# Sheet3_Fontes_Chaveadas_Fontes_Aux.net
KiCad netlist of a schematic drawn in Altium Designer
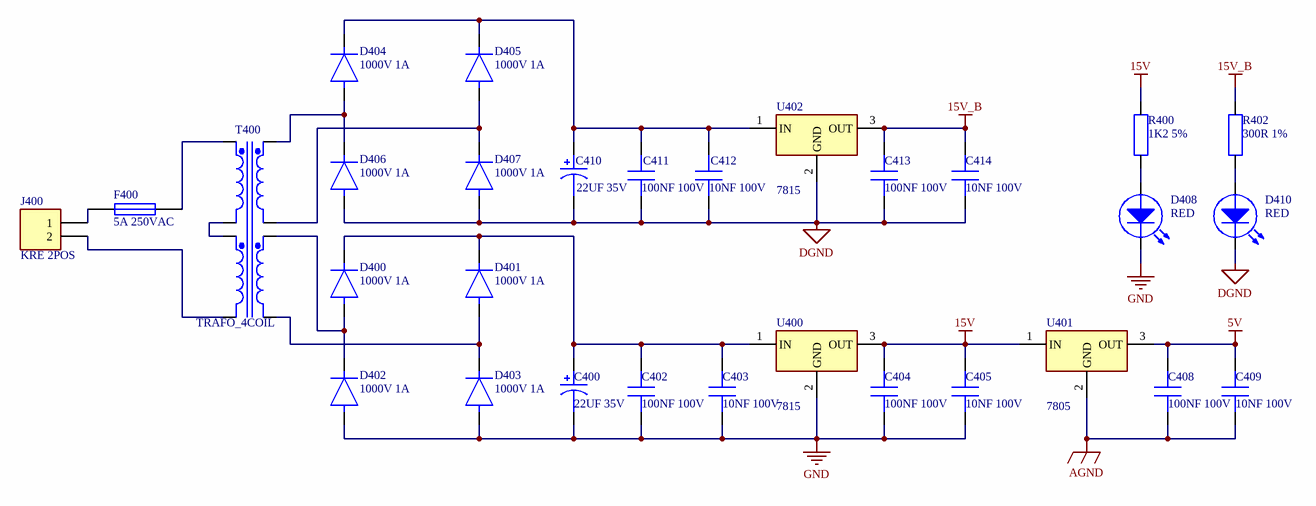
[diagram p0: Sheet3_Fontes_Chaveadas_Fontes_Aux.SchDoc]

(export (version "E")
  (design (tool "Eeschema 10.0.6"))
  (components
    (comp (ref "C400")
      (value "22UF 35V")
      (footprint "PcbLib_Fontes_Chaveadas:CAP_RAD_D6MM3_L2MM5")
      (description "CAP ALUM POLY 22UF 20% 35V T/H")
      (fields (field (name "PARTNUMBER") "870055673002") (field (name "DKPART") "732-6368-1-ND"))
      (libsource (lib "Schlib_Fontes_Chaveadas") (part "CAP_ALUM_22UF_35V_RAD"))
    )
    (comp (ref "C402")
      (value "100NF 100V")
      (footprint "PcbLib_Fontes_Chaveadas:CAP_RAD_4X2MM5")
      (description "CAP CER 0.1UF 100V X7S RADIAL")
      (fields (field (name "PARTNUMBER") "FG18X7S2A104KRT06") (field (name "DKPART") "445-173281-1-ND"))
      (libsource (lib "Schlib_Fontes_Chaveadas") (part "CAP_CER_100NF_100V_RAD"))
    )
    (comp (ref "C403")
      (value "10NF 100V")
      (footprint "PcbLib_Fontes_Chaveadas:CAP_RAD_4X2MM5")
      (description "CAP CER 10NF 100V C0G/NP0 RADIAL")
      (fields (field (name "PARTNUMBER") "FA18C0G2A103JRU06") (field (name "DKPART") "445-175393-1-ND"))
      (libsource (lib "Schlib_Fontes_Chaveadas") (part "CAP_CER_10NF_100V_RAD"))
    )
    (comp (ref "C404")
      (value "100NF 100V")
      (footprint "PcbLib_Fontes_Chaveadas:CAP_RAD_4X2MM5")
      (description "CAP CER 0.1UF 100V X7S RADIAL")
      (fields (field (name "PARTNUMBER") "FG18X7S2A104KRT06") (field (name "DKPART") "445-173281-1-ND"))
      (libsource (lib "Schlib_Fontes_Chaveadas") (part "CAP_CER_100NF_100V_RAD"))
    )
    (comp (ref "C405")
      (value "10NF 100V")
      (footprint "PcbLib_Fontes_Chaveadas:CAP_RAD_4X2MM5")
      (description "CAP CER 10NF 100V C0G/NP0 RADIAL")
      (fields (field (name "PARTNUMBER") "FA18C0G2A103JRU06") (field (name "DKPART") "445-175393-1-ND"))
      (libsource (lib "Schlib_Fontes_Chaveadas") (part "CAP_CER_10NF_100V_RAD"))
    )
    (comp (ref "C408")
      (value "100NF 100V")
      (footprint "PcbLib_Fontes_Chaveadas:CAP_RAD_4X2MM5")
      (description "CAP CER 0.1UF 100V X7S RADIAL")
      (fields (field (name "PARTNUMBER") "FG18X7S2A104KRT06") (field (name "DKPART") "445-173281-1-ND"))
      (libsource (lib "Schlib_Fontes_Chaveadas") (part "CAP_CER_100NF_100V_RAD"))
    )
    (comp (ref "C409")
      (value "10NF 100V")
      (footprint "PcbLib_Fontes_Chaveadas:CAP_RAD_4X2MM5")
      (description "CAP CER 10NF 100V C0G/NP0 RADIAL")
      (fields (field (name "PARTNUMBER") "FA18C0G2A103JRU06") (field (name "DKPART") "445-175393-1-ND"))
      (libsource (lib "Schlib_Fontes_Chaveadas") (part "CAP_CER_10NF_100V_RAD"))
    )
    (comp (ref "C410")
      (value "22UF 35V")
      (footprint "PcbLib_Fontes_Chaveadas:CAP_RAD_D6MM3_L2MM5")
      (description "CAP ALUM POLY 22UF 20% 35V T/H")
      (fields (field (name "PARTNUMBER") "870055673002") (field (name "DKPART") "732-6368-1-ND"))
      (libsource (lib "Schlib_Fontes_Chaveadas") (part "CAP_ALUM_22UF_35V_RAD"))
    )
    (comp (ref "C411")
      (value "100NF 100V")
      (footprint "PcbLib_Fontes_Chaveadas:CAP_RAD_4X2MM5")
      (description "CAP CER 0.1UF 100V X7S RADIAL")
      (fields (field (name "PARTNUMBER") "FG18X7S2A104KRT06") (field (name "DKPART") "445-173281-1-ND"))
      (libsource (lib "Schlib_Fontes_Chaveadas") (part "CAP_CER_100NF_100V_RAD"))
    )
    (comp (ref "C412")
      (value "10NF 100V")
      (footprint "PcbLib_Fontes_Chaveadas:CAP_RAD_4X2MM5")
      (description "CAP CER 10NF 100V C0G/NP0 RADIAL")
      (fields (field (name "PARTNUMBER") "FA18C0G2A103JRU06") (field (name "DKPART") "445-175393-1-ND"))
      (libsource (lib "Schlib_Fontes_Chaveadas") (part "CAP_CER_10NF_100V_RAD"))
    )
    (comp (ref "C413")
      (value "100NF 100V")
      (footprint "PcbLib_Fontes_Chaveadas:CAP_RAD_4X2MM5")
      (description "CAP CER 0.1UF 100V X7S RADIAL")
      (fields (field (name "PARTNUMBER") "FG18X7S2A104KRT06") (field (name "DKPART") "445-173281-1-ND"))
      (libsource (lib "Schlib_Fontes_Chaveadas") (part "CAP_CER_100NF_100V_RAD"))
    )
    (comp (ref "C414")
      (value "10NF 100V")
      (footprint "PcbLib_Fontes_Chaveadas:CAP_RAD_4X2MM5")
      (description "CAP CER 10NF 100V C0G/NP0 RADIAL")
      (fields (field (name "PARTNUMBER") "FA18C0G2A103JRU06") (field (name "DKPART") "445-175393-1-ND"))
      (libsource (lib "Schlib_Fontes_Chaveadas") (part "CAP_CER_10NF_100V_RAD"))
    )
    (comp (ref "D400")
      (value "1000V 1A")
      (footprint "PcbLib_Fontes_Chaveadas:DIO_PTH_DO41_1N4007")
      (description "DIODE GEN PURP 1KV 1A DO41")
      (fields (field (name "PARTNUMBER") "1N4007-TP") (field (name "DKPART") "1N4007-TPMSCT-ND"))
      (libsource (lib "Schlib_Fontes_Chaveadas") (part "DIO_PTH_STD_1000V_1A_1N4007"))
    )
    (comp (ref "D401")
      (value "1000V 1A")
      (footprint "PcbLib_Fontes_Chaveadas:DIO_PTH_DO41_1N4007")
      (description "DIODE GEN PURP 1KV 1A DO41")
      (fields (field (name "PARTNUMBER") "1N4007-TP") (field (name "DKPART") "1N4007-TPMSCT-ND"))
      (libsource (lib "Schlib_Fontes_Chaveadas") (part "DIO_PTH_STD_1000V_1A_1N4007"))
    )
    (comp (ref "D402")
      (value "1000V 1A")
      (footprint "PcbLib_Fontes_Chaveadas:DIO_PTH_DO41_1N4007")
      (description "DIODE GEN PURP 1KV 1A DO41")
      (fields (field (name "PARTNUMBER") "1N4007-TP") (field (name "DKPART") "1N4007-TPMSCT-ND"))
      (libsource (lib "Schlib_Fontes_Chaveadas") (part "DIO_PTH_STD_1000V_1A_1N4007"))
    )
    (comp (ref "D403")
      (value "1000V 1A")
      (footprint "PcbLib_Fontes_Chaveadas:DIO_PTH_DO41_1N4007")
      (description "DIODE GEN PURP 1KV 1A DO41")
      (fields (field (name "PARTNUMBER") "1N4007-TP") (field (name "DKPART") "1N4007-TPMSCT-ND"))
      (libsource (lib "Schlib_Fontes_Chaveadas") (part "DIO_PTH_STD_1000V_1A_1N4007"))
    )
    (comp (ref "D404")
      (value "1000V 1A")
      (footprint "PcbLib_Fontes_Chaveadas:DIO_PTH_DO41_1N4007")
      (description "DIODE GEN PURP 1KV 1A DO41")
      (fields (field (name "PARTNUMBER") "1N4007-TP") (field (name "DKPART") "1N4007-TPMSCT-ND"))
      (libsource (lib "Schlib_Fontes_Chaveadas") (part "DIO_PTH_STD_1000V_1A_1N4007"))
    )
    (comp (ref "D405")
      (value "1000V 1A")
      (footprint "PcbLib_Fontes_Chaveadas:DIO_PTH_DO41_1N4007")
      (description "DIODE GEN PURP 1KV 1A DO41")
      (fields (field (name "PARTNUMBER") "1N4007-TP") (field (name "DKPART") "1N4007-TPMSCT-ND"))
      (libsource (lib "Schlib_Fontes_Chaveadas") (part "DIO_PTH_STD_1000V_1A_1N4007"))
    )
    (comp (ref "D406")
      (value "1000V 1A")
      (footprint "PcbLib_Fontes_Chaveadas:DIO_PTH_DO41_1N4007")
      (description "DIODE GEN PURP 1KV 1A DO41")
      (fields (field (name "PARTNUMBER") "1N4007-TP") (field (name "DKPART") "1N4007-TPMSCT-ND"))
      (libsource (lib "Schlib_Fontes_Chaveadas") (part "DIO_PTH_STD_1000V_1A_1N4007"))
    )
    (comp (ref "D407")
      (value "1000V 1A")
      (footprint "PcbLib_Fontes_Chaveadas:DIO_PTH_DO41_1N4007")
      (description "DIODE GEN PURP 1KV 1A DO41")
      (fields (field (name "PARTNUMBER") "1N4007-TP") (field (name "DKPART") "1N4007-TPMSCT-ND"))
      (libsource (lib "Schlib_Fontes_Chaveadas") (part "DIO_PTH_STD_1000V_1A_1N4007"))
    )
    (comp (ref "D408")
      (value "RED")
      (footprint "PcbLib_Fontes_Chaveadas:DIO_PTH_LED_RED")
      (description "LED RED DIFFUSED T-1 3/4 T/H")
      (fields (field (name "PARTNUMBER") "XLUR12D") (field (name "DKPART") "1497-1031-ND"))
      (libsource (lib "Schlib_Fontes_Chaveadas") (part "DIO_PTH_LED_RED_5MM"))
    )
    (comp (ref "D410")
      (value "RED")
      (footprint "PcbLib_Fontes_Chaveadas:DIO_PTH_LED_RED")
      (description "LED RED DIFFUSED T-1 3/4 T/H")
      (fields (field (name "PARTNUMBER") "XLUR12D") (field (name "DKPART") "1497-1031-ND"))
      (libsource (lib "Schlib_Fontes_Chaveadas") (part "DIO_PTH_LED_RED_5MM"))
    )
    (comp (ref "F400")
      (value "5A 250VAC")
      (footprint "PcbLib_Fontes_Chaveadas:FUSE_PTH_5X20MM")
      (description "FUSE GLASS 5A 250VAC 5X20MM")
      (fields (field (name "PARTNUMBER") "5STP 5-R") (field (name "DKPART") "507-1561-ND"))
      (libsource (lib "Schlib_Fontes_Chaveadas") (part "FUSE_PTH_5A_250VAC"))
    )
    (comp (ref "J400")
      (value "KRE 2POS")
      (footprint "PcbLib_Fontes_Chaveadas:CONN_KF3012P")
      (description "TERM BLK 2POS SIDE ENTRY 5MM PCB")
      (fields (field (name "PARTNUMBER") "1776244-2") (field (name "DKPART") "A97996-ND"))
      (libsource (lib "Schlib_Fontes_Chaveadas") (part "CONN_2POS"))
    )
    (comp (ref "R400")
      (value "1K2 5%")
      (footprint "PcbLib_Fontes_Chaveadas:RES_PTH_AXIAL_250MW")
      (description "RES 1.2K OHM 5% 1/4W AXIAL")
      (fields (field (name "PARTNUMBER") "CFR-25JB-52-1K2") (field (name "DKPART") "1.2KQBK-ND"))
      (libsource (lib "Schlib_Fontes_Chaveadas") (part "RES_1K2_5%_250MW_AXIAL"))
    )
    (comp (ref "R402")
      (value "300R 1%")
      (footprint "PcbLib_Fontes_Chaveadas:RES_PTH_AXIAL_250MW")
      (description "RES 300 OHM 1% 1/4W AXIAL")
      (fields (field (name "PARTNUMBER") "RNMF14FTC300R") (field (name "DKPART") "S300CACT-ND"))
      (libsource (lib "Schlib_Fontes_Chaveadas") (part "RES_300R_1%_250MW_AXIAL"))
    )
    (comp (ref "T400")
      (value "TRAFO_4COIL")
      (footprint "PcbLib_Fontes_Chaveadas:TRF_8")
      (description "TRANSFORMER 4 COILS")
      (fields (field (name "PARTNUMBER") "_TRAFO_02") (field (name "MANUFACTURER") "UNIFOR"))
      (libsource (lib "Schlib_Fontes_Chaveadas") (part "TRANSFORMER_4WINDING"))
    )
    (comp (ref "U400")
      (value "7815")
      (footprint "PcbLib_Fontes_Chaveadas:PTH_TO220AB")
      (description "IC REG LINEAR 15V 1.5A TO220AB")
      (fields (field (name "DKPART") "497-1454-5-ND") (field (name "MANUFACTURER") "STMicroelectronics"))
      (libsource (lib "Schlib_Fontes_Chaveadas") (part "IC_LM7815"))
    )
    (comp (ref "U401")
      (value "7805")
      (footprint "PcbLib_Fontes_Chaveadas:PTH_TO220AB")
      (description "IC REG LINEAR 5V 1.5A TO220AB")
      (fields (field (name "DKPART") "497-1443-5-ND") (field (name "MANUFACTURER") "STMicroelectronics"))
      (libsource (lib "Schlib_Fontes_Chaveadas") (part "IC_LM7805"))
    )
    (comp (ref "U402")
      (value "7815")
      (footprint "PcbLib_Fontes_Chaveadas:PTH_TO220AB")
      (description "IC REG LINEAR 15V 1.5A TO220AB")
      (fields (field (name "DKPART") "497-1454-5-ND") (field (name "MANUFACTURER") "STMicroelectronics"))
      (libsource (lib "Schlib_Fontes_Chaveadas") (part "IC_LM7815"))
    )
  )
  (nets
    (net (code "1") (name "5V") (class "Default")
      (node (ref "C408") (pin "1") (pinfunction "1_1") (pintype "passive"))
      (node (ref "C409") (pin "1") (pinfunction "1_1") (pintype "passive"))
      (node (ref "U401") (pin "3") (pinfunction "OUT_3") (pintype "power_in"))
    )
    (net (code "2") (name "15V") (class "Default")
      (node (ref "C404") (pin "1") (pinfunction "1_1") (pintype "passive"))
      (node (ref "C405") (pin "1") (pinfunction "1_1") (pintype "passive"))
      (node (ref "R400") (pin "1") (pinfunction "1_1") (pintype "passive"))
      (node (ref "U400") (pin "3") (pinfunction "OUT_3") (pintype "power_in"))
      (node (ref "U401") (pin "1") (pinfunction "IN_1") (pintype "power_in"))
    )
    (net (code "3") (name "15V_B") (class "Default")
      (node (ref "C413") (pin "1") (pinfunction "1_1") (pintype "passive"))
      (node (ref "C414") (pin "1") (pinfunction "1_1") (pintype "passive"))
      (node (ref "R402") (pin "1") (pinfunction "1_1") (pintype "passive"))
      (node (ref "U402") (pin "3") (pinfunction "OUT_3") (pintype "power_in"))
    )
    (net (code "4") (name "AGND") (class "Default")
      (node (ref "C408") (pin "2") (pinfunction "2_2") (pintype "passive"))
      (node (ref "C409") (pin "2") (pinfunction "2_2") (pintype "passive"))
      (node (ref "U401") (pin "2") (pinfunction "GND_2") (pintype "power_in"))
    )
    (net (code "5") (name "DGND") (class "Default")
      (node (ref "C410") (pin "2") (pinfunction "-_2") (pintype "passive"))
      (node (ref "C411") (pin "2") (pinfunction "2_2") (pintype "passive"))
      (node (ref "C412") (pin "2") (pinfunction "2_2") (pintype "passive"))
      (node (ref "C413") (pin "2") (pinfunction "2_2") (pintype "passive"))
      (node (ref "C414") (pin "2") (pinfunction "2_2") (pintype "passive"))
      (node (ref "D406") (pin "2") (pinfunction "A_2") (pintype "passive"))
      (node (ref "D407") (pin "2") (pinfunction "A_2") (pintype "passive"))
      (node (ref "D410") (pin "2") (pinfunction "K_2") (pintype "passive"))
      (node (ref "U402") (pin "2") (pinfunction "GND_2") (pintype "power_in"))
    )
    (net (code "6") (name "GND") (class "Default")
      (node (ref "C400") (pin "2") (pinfunction "-_2") (pintype "passive"))
      (node (ref "C402") (pin "2") (pinfunction "2_2") (pintype "passive"))
      (node (ref "C403") (pin "2") (pinfunction "2_2") (pintype "passive"))
      (node (ref "C404") (pin "2") (pinfunction "2_2") (pintype "passive"))
      (node (ref "C405") (pin "2") (pinfunction "2_2") (pintype "passive"))
      (node (ref "D402") (pin "2") (pinfunction "A_2") (pintype "passive"))
      (node (ref "D403") (pin "2") (pinfunction "A_2") (pintype "passive"))
      (node (ref "D408") (pin "2") (pinfunction "K_2") (pintype "passive"))
      (node (ref "U400") (pin "2") (pinfunction "GND_2") (pintype "power_in"))
    )
    (net (code "7") (name "Net-(C400-+)") (class "Default")
      (node (ref "C400") (pin "1") (pinfunction "+_1") (pintype "passive"))
      (node (ref "C402") (pin "1") (pinfunction "1_1") (pintype "passive"))
      (node (ref "C403") (pin "1") (pinfunction "1_1") (pintype "passive"))
      (node (ref "D400") (pin "1") (pinfunction "K_1") (pintype "passive"))
      (node (ref "D401") (pin "1") (pinfunction "K_1") (pintype "passive"))
      (node (ref "U400") (pin "1") (pinfunction "IN_1") (pintype "power_in"))
    )
    (net (code "8") (name "Net-(C410-+)") (class "Default")
      (node (ref "C410") (pin "1") (pinfunction "+_1") (pintype "passive"))
      (node (ref "C411") (pin "1") (pinfunction "1_1") (pintype "passive"))
      (node (ref "C412") (pin "1") (pinfunction "1_1") (pintype "passive"))
      (node (ref "D404") (pin "1") (pinfunction "K_1") (pintype "passive"))
      (node (ref "D405") (pin "1") (pinfunction "K_1") (pintype "passive"))
      (node (ref "U402") (pin "1") (pinfunction "IN_1") (pintype "power_in"))
    )
    (net (code "9") (name "Net-(D400-A)") (class "Default")
      (node (ref "D400") (pin "2") (pinfunction "A_2") (pintype "passive"))
      (node (ref "D402") (pin "1") (pinfunction "K_1") (pintype "passive"))
      (node (ref "T400") (pin "7") (pinfunction "Sec2+_7") (pintype "passive"))
    )
    (net (code "10") (name "Net-(D401-A)") (class "Default")
      (node (ref "D401") (pin "2") (pinfunction "A_2") (pintype "passive"))
      (node (ref "D403") (pin "1") (pinfunction "K_1") (pintype "passive"))
      (node (ref "T400") (pin "8") (pinfunction "Sec2-_8") (pintype "passive"))
    )
    (net (code "11") (name "Net-(D404-A)") (class "Default")
      (node (ref "D404") (pin "2") (pinfunction "A_2") (pintype "passive"))
      (node (ref "D406") (pin "1") (pinfunction "K_1") (pintype "passive"))
      (node (ref "T400") (pin "5") (pinfunction "Sec1+_5") (pintype "passive"))
    )
    (net (code "12") (name "Net-(D405-A)") (class "Default")
      (node (ref "D405") (pin "2") (pinfunction "A_2") (pintype "passive"))
      (node (ref "D407") (pin "1") (pinfunction "K_1") (pintype "passive"))
      (node (ref "T400") (pin "6") (pinfunction "Sec1-_6") (pintype "passive"))
    )
    (net (code "13") (name "Net-(D408-A)") (class "Default")
      (node (ref "D408") (pin "1") (pinfunction "A_1") (pintype "passive"))
      (node (ref "R400") (pin "2") (pinfunction "2_2") (pintype "passive"))
    )
    (net (code "14") (name "Net-(D410-A)") (class "Default")
      (node (ref "D410") (pin "1") (pinfunction "A_1") (pintype "passive"))
      (node (ref "R402") (pin "2") (pinfunction "2_2") (pintype "passive"))
    )
    (net (code "15") (name "Net-(F400-Pad1)") (class "Default")
      (node (ref "F400") (pin "1") (pinfunction "1_1") (pintype "passive"))
      (node (ref "J400") (pin "1") (pinfunction "1_1") (pintype "passive"))
    )
    (net (code "16") (name "Net-(T400-Pri+)") (class "Default")
      (node (ref "F400") (pin "2") (pinfunction "2_2") (pintype "passive"))
      (node (ref "T400") (pin "1") (pinfunction "Pri+_1") (pintype "passive"))
    )
    (net (code "17") (name "Net-(T400-Pri-)") (class "Default")
      (node (ref "T400") (pin "2") (pinfunction "Pri-_2") (pintype "passive"))
      (node (ref "T400") (pin "3") (pinfunction "Pri2+_3") (pintype "passive"))
    )
    (net (code "18") (name "Net-(T400-Pri2-)") (class "Default")
      (node (ref "J400") (pin "2") (pinfunction "2_2") (pintype "passive"))
      (node (ref "T400") (pin "4") (pinfunction "Pri2-_4") (pintype "passive"))
    )
  )
)
